# TR808_Project-2.net
KiCad netlist of a schematic drawn in EAGLE
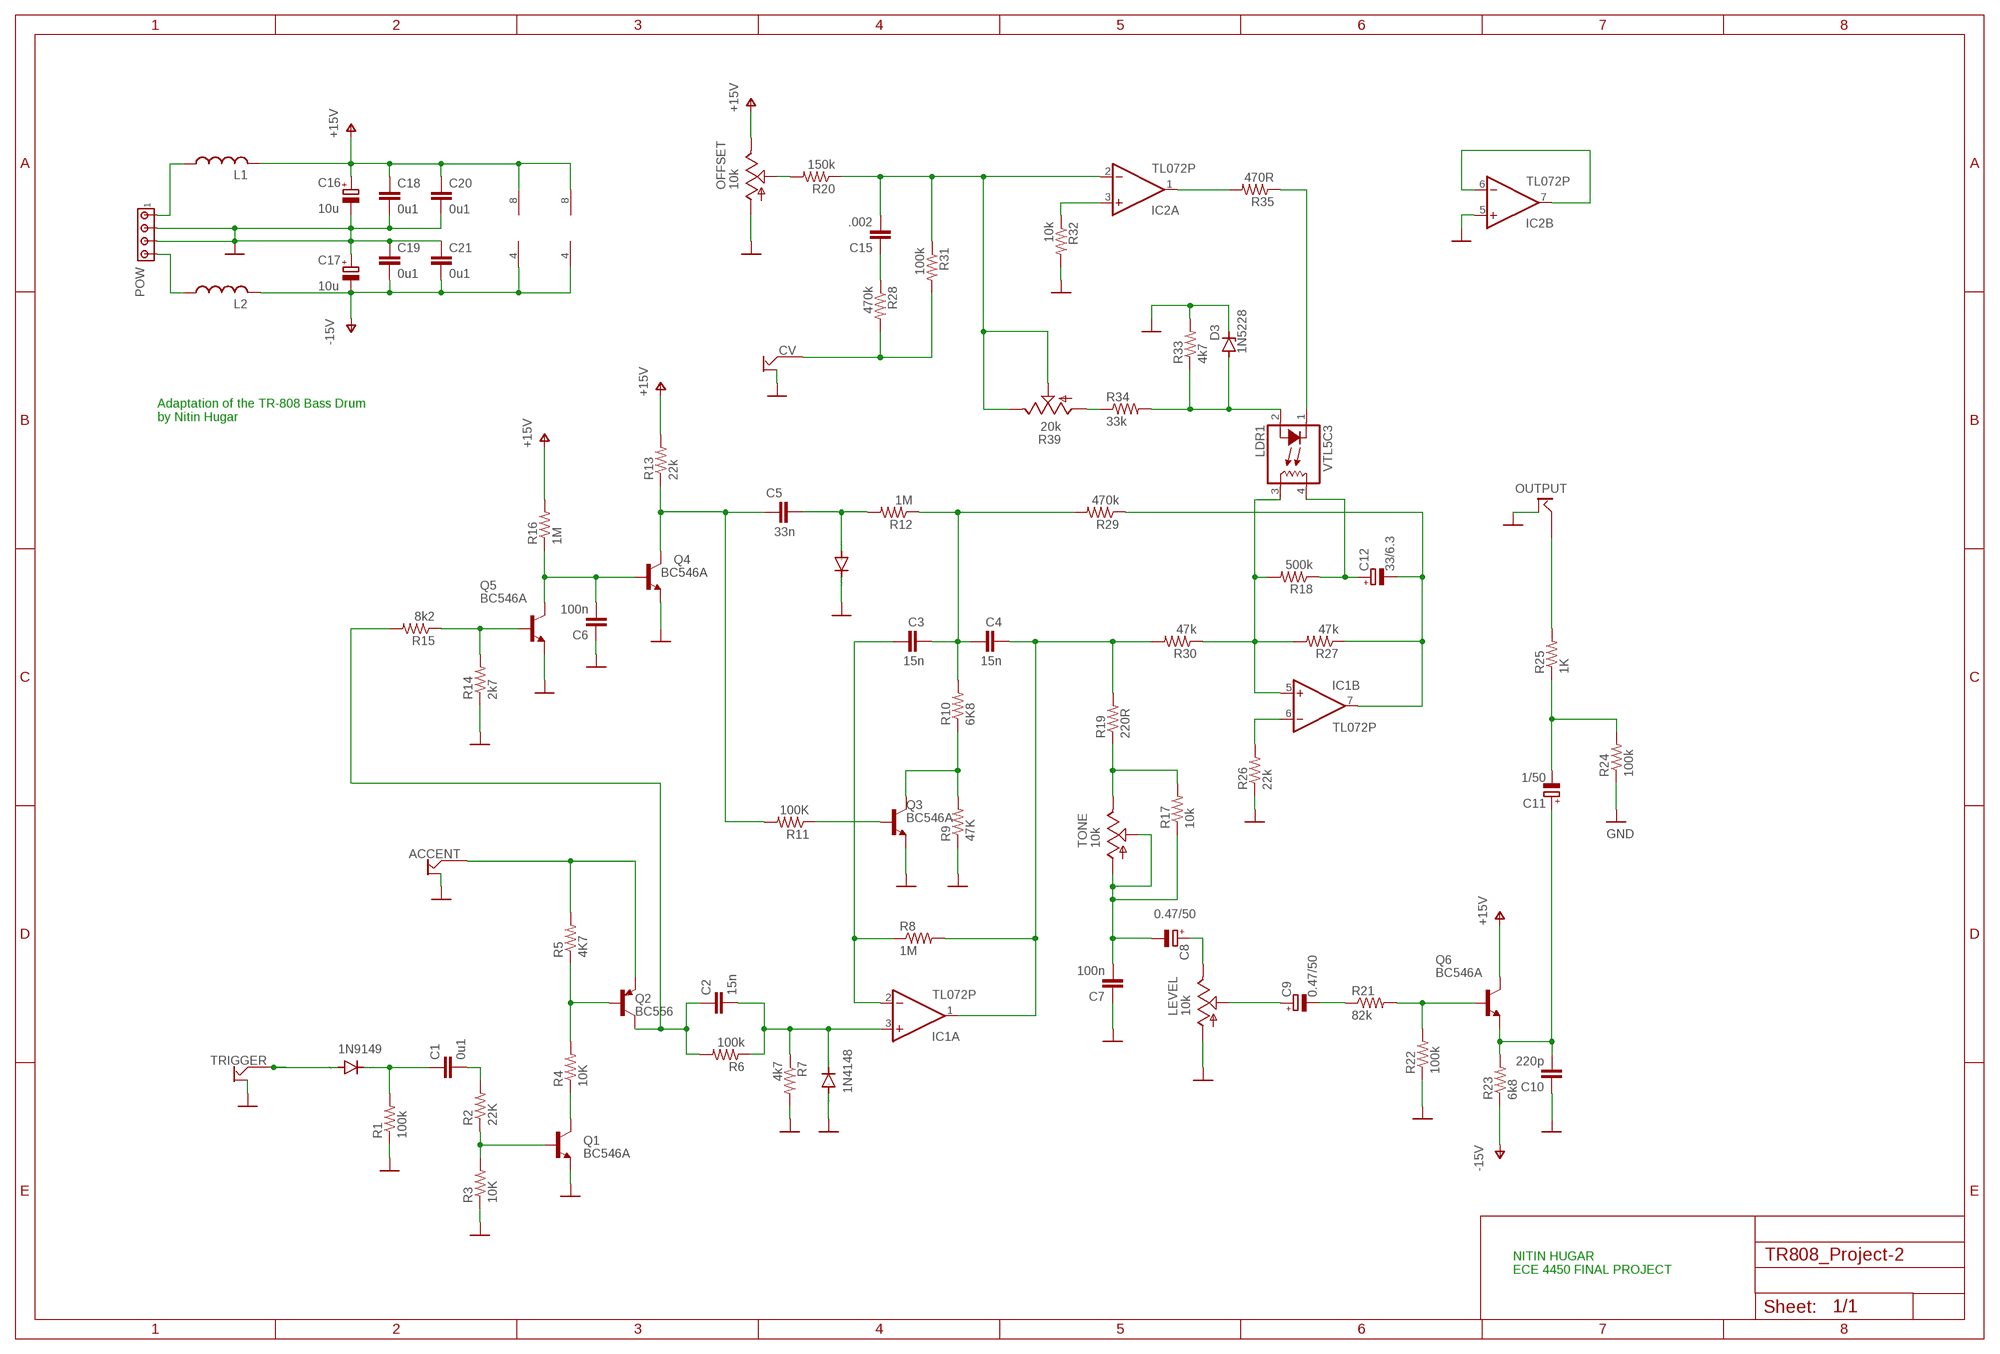
[diagram p0: schematic, sheet 1]

(export (version "E")
  (design (tool "Eeschema 10.0.6"))
  (components
    (comp (ref "1N4148")
      (value "1N4148")
      (footprint "eagle-import:DO35-10")
      (libsource (lib "eagle-import") (part "1N4148DO35-10"))
    )
    (comp (ref "ACCENT")
      (value "OFFBOARD2JACKALT_AARON")
      (footprint "eagle-import:OFFBOARD2JACKALT")
      (libsource (lib "eagle-import") (part "OFFBOARD2JACKALT_AARON"))
    )
    (comp (ref "C1")
      (value "0u1")
      (footprint "eagle-import:C050-025X075")
      (libsource (lib "eagle-import") (part "C-EU050-025X075"))
    )
    (comp (ref "C2")
      (value "15n")
      (footprint "eagle-import:C050-025X075")
      (libsource (lib "eagle-import") (part "C-EU050-025X075"))
    )
    (comp (ref "C3")
      (value "15n")
      (footprint "eagle-import:C050-025X075")
      (libsource (lib "eagle-import") (part "C-EU050-025X075"))
    )
    (comp (ref "C4")
      (value "15n")
      (footprint "eagle-import:C050-025X075")
      (libsource (lib "eagle-import") (part "C-EU050-025X075"))
    )
    (comp (ref "C5")
      (value "33n")
      (footprint "eagle-import:C050-025X075")
      (libsource (lib "eagle-import") (part "C-EU050-025X075"))
    )
    (comp (ref "C6")
      (value "100n")
      (footprint "eagle-import:C050-025X075")
      (libsource (lib "eagle-import") (part "C-EU050-025X075"))
    )
    (comp (ref "C7")
      (value "100n")
      (footprint "eagle-import:C050-025X075")
      (libsource (lib "eagle-import") (part "C-EU050-025X075"))
    )
    (comp (ref "C8")
      (value "0.47/50")
      (footprint "eagle-import:E1,8-4")
      (libsource (lib "eagle-import") (part "CPOL-EUE1.8-4"))
    )
    (comp (ref "C9")
      (value "0.47/50")
      (footprint "eagle-import:E1,8-4")
      (libsource (lib "eagle-import") (part "CPOL-EUE1.8-4"))
    )
    (comp (ref "C10")
      (value "220p")
      (footprint "eagle-import:C050-025X075")
      (libsource (lib "eagle-import") (part "C-EU050-025X075"))
    )
    (comp (ref "C11")
      (value "1/50")
      (footprint "eagle-import:E1,8-4")
      (libsource (lib "eagle-import") (part "CPOL-EUE1.8-4"))
    )
    (comp (ref "C12")
      (value "33/6.3")
      (footprint "eagle-import:E1,8-4")
      (libsource (lib "eagle-import") (part "CPOL-EUE1.8-4"))
    )
    (comp (ref "C15")
      (value ".002")
      (footprint "eagle-import:C050-025X075")
      (libsource (lib "eagle-import") (part "C-EU050-025X075"))
    )
    (comp (ref "C16")
      (value "10u")
      (footprint "eagle-import:E1,8-4")
      (libsource (lib "eagle-import") (part "CPOL-EUE1.8-4"))
    )
    (comp (ref "C17")
      (value "10u")
      (footprint "eagle-import:E1,8-4")
      (libsource (lib "eagle-import") (part "CPOL-EUE1.8-4"))
    )
    (comp (ref "C18")
      (value "0u1")
      (footprint "eagle-import:C050-025X075")
      (libsource (lib "eagle-import") (part "C-EU050-025X075"))
    )
    (comp (ref "C19")
      (value "0u1")
      (footprint "eagle-import:C050-025X075")
      (libsource (lib "eagle-import") (part "C-EU050-025X075"))
    )
    (comp (ref "C20")
      (value "0u1")
      (footprint "eagle-import:C050-025X075")
      (libsource (lib "eagle-import") (part "C-EU050-025X075"))
    )
    (comp (ref "C21")
      (value "0u1")
      (footprint "eagle-import:C050-025X075")
      (libsource (lib "eagle-import") (part "C-EU050-025X075"))
    )
    (comp (ref "CV")
      (value "OFFBOARD2JACKALT_AARON")
      (footprint "eagle-import:OFFBOARD2JACKALT")
      (libsource (lib "eagle-import") (part "OFFBOARD2JACKALT_AARON"))
    )
    (comp (ref "D1")
      (value "1N9149")
      (footprint "eagle-import:D-10")
      (libsource (lib "eagle-import") (part "DIODE-D-10"))
    )
    (comp (ref "D2")
      (value "1N4148")
      (footprint "eagle-import:DO35-10")
      (libsource (lib "eagle-import") (part "1N4148DO35-10"))
    )
    (comp (ref "D3")
      (value "1N5228")
      (footprint "eagle-import:C1702-15")
      (libsource (lib "eagle-import") (part "ZENER-DIODEC1702-15"))
    )
    (comp (ref "IC1")
      (value "TL072P")
      (footprint "eagle-import:DIL08")
      (libsource (lib "eagle-import") (part "TL072P"))
    )
    (comp (ref "IC2")
      (value "TL072P")
      (footprint "eagle-import:DIL08")
      (libsource (lib "eagle-import") (part "TL072P"))
    )
    (comp (ref "L1")
      (value "L-US0207/10")
      (footprint "eagle-import:0207_10")
      (libsource (lib "eagle-import") (part "L-US0207/10"))
    )
    (comp (ref "L2")
      (value "L-US0207/10")
      (footprint "eagle-import:0207_10")
      (libsource (lib "eagle-import") (part "L-US0207/10"))
    )
    (comp (ref "LDR1")
      (value "VTL5C3")
      (footprint "eagle-import:VTL5C")
      (fields (field (name "MF") "VACTEC PHOTO") (field (name "MPN") "VTL5C9"))
      (libsource (lib "eagle-import") (part "VTL5C9"))
    )
    (comp (ref "LEVEL")
      (value "10k")
      (footprint "eagle-import:B64Y")
      (libsource (lib "eagle-import") (part "TRIM_US-B64Y"))
    )
    (comp (ref "OFFSET")
      (value "10k")
      (footprint "eagle-import:B64Y")
      (libsource (lib "eagle-import") (part "TRIM_US-B64Y"))
    )
    (comp (ref "OUTPUT")
      (value "OFFBOARD2JACKALT_AARON")
      (footprint "eagle-import:OFFBOARD2JACKALT")
      (libsource (lib "eagle-import") (part "OFFBOARD2JACKALT_AARON"))
    )
    (comp (ref "POW")
      (value "MTA04-156")
      (footprint "eagle-import:1X4MTA")
      (libsource (lib "eagle-import") (part "MTA04-156"))
    )
    (comp (ref "Q1")
      (value "BC546A")
      (footprint "eagle-import:TO92-EBC")
      (libsource (lib "eagle-import") (part "BC546A"))
    )
    (comp (ref "Q2")
      (value "BC556")
      (footprint "eagle-import:TO92-EBC")
      (libsource (lib "eagle-import") (part "BC556"))
    )
    (comp (ref "Q3")
      (value "BC546A")
      (footprint "eagle-import:TO92-EBC")
      (libsource (lib "eagle-import") (part "BC546A"))
    )
    (comp (ref "Q4")
      (value "BC546A")
      (footprint "eagle-import:TO92-EBC")
      (libsource (lib "eagle-import") (part "BC546A"))
    )
    (comp (ref "Q5")
      (value "BC546A")
      (footprint "eagle-import:TO92-EBC")
      (libsource (lib "eagle-import") (part "BC546A"))
    )
    (comp (ref "Q6")
      (value "BC546A")
      (footprint "eagle-import:TO92-EBC")
      (libsource (lib "eagle-import") (part "BC546A"))
    )
    (comp (ref "R1")
      (value "100k")
      (footprint "eagle-import:0207_10")
      (libsource (lib "eagle-import") (part "R-US_0207/10"))
    )
    (comp (ref "R2")
      (value "22K")
      (footprint "eagle-import:0207_10")
      (libsource (lib "eagle-import") (part "R-US_0207/10"))
    )
    (comp (ref "R3")
      (value "10K")
      (footprint "eagle-import:0207_10")
      (libsource (lib "eagle-import") (part "R-US_0207/10"))
    )
    (comp (ref "R4")
      (value "10K")
      (footprint "eagle-import:0207_10")
      (libsource (lib "eagle-import") (part "R-US_0207/10"))
    )
    (comp (ref "R5")
      (value "4K7")
      (footprint "eagle-import:0207_10")
      (libsource (lib "eagle-import") (part "R-US_0207/10"))
    )
    (comp (ref "R6")
      (value "100k")
      (footprint "eagle-import:0207_10")
      (libsource (lib "eagle-import") (part "R-US_0207/10"))
    )
    (comp (ref "R7")
      (value "4k7")
      (footprint "eagle-import:0207_10")
      (libsource (lib "eagle-import") (part "R-US_0207/10"))
    )
    (comp (ref "R8")
      (value "1M")
      (footprint "eagle-import:0207_10")
      (libsource (lib "eagle-import") (part "R-US_0207/10"))
    )
    (comp (ref "R9")
      (value "47K")
      (footprint "eagle-import:0207_10")
      (libsource (lib "eagle-import") (part "R-US_0207/10"))
    )
    (comp (ref "R10")
      (value "6K8")
      (footprint "eagle-import:0207_10")
      (libsource (lib "eagle-import") (part "R-US_0207/10"))
    )
    (comp (ref "R11")
      (value "100K")
      (footprint "eagle-import:0207_10")
      (libsource (lib "eagle-import") (part "R-US_0207/10"))
    )
    (comp (ref "R12")
      (value "1M")
      (footprint "eagle-import:0207_10")
      (libsource (lib "eagle-import") (part "R-US_0207/10"))
    )
    (comp (ref "R13")
      (value "22k")
      (footprint "eagle-import:0207_10")
      (libsource (lib "eagle-import") (part "R-US_0207/10"))
    )
    (comp (ref "R14")
      (value "2k7")
      (footprint "eagle-import:0207_10")
      (libsource (lib "eagle-import") (part "R-US_0207/10"))
    )
    (comp (ref "R15")
      (value "8k2")
      (footprint "eagle-import:0207_10")
      (libsource (lib "eagle-import") (part "R-US_0207/10"))
    )
    (comp (ref "R16")
      (value "1M")
      (footprint "eagle-import:0207_10")
      (libsource (lib "eagle-import") (part "R-US_0207/10"))
    )
    (comp (ref "R17")
      (value "10k")
      (footprint "eagle-import:0207_10")
      (libsource (lib "eagle-import") (part "R-US_0207/10"))
    )
    (comp (ref "R18")
      (value "500k")
      (footprint "eagle-import:0207_10")
      (libsource (lib "eagle-import") (part "R-US_0207/10"))
    )
    (comp (ref "R19")
      (value "220R")
      (footprint "eagle-import:0207_10")
      (libsource (lib "eagle-import") (part "R-US_0207/10"))
    )
    (comp (ref "R20")
      (value "150k")
      (footprint "eagle-import:0207_10")
      (libsource (lib "eagle-import") (part "R-US_0207/10"))
    )
    (comp (ref "R21")
      (value "82k")
      (footprint "eagle-import:0207_10")
      (libsource (lib "eagle-import") (part "R-US_0207/10"))
    )
    (comp (ref "R22")
      (value "100k")
      (footprint "eagle-import:0207_10")
      (libsource (lib "eagle-import") (part "R-US_0207/10"))
    )
    (comp (ref "R23")
      (value "6k8")
      (footprint "eagle-import:0207_10")
      (libsource (lib "eagle-import") (part "R-US_0207/10"))
    )
    (comp (ref "R24")
      (value "100k")
      (footprint "eagle-import:0207_10")
      (libsource (lib "eagle-import") (part "R-US_0207/10"))
    )
    (comp (ref "R25")
      (value "1K")
      (footprint "eagle-import:0207_10")
      (libsource (lib "eagle-import") (part "R-US_0207/10"))
    )
    (comp (ref "R26")
      (value "22k")
      (footprint "eagle-import:0207_10")
      (libsource (lib "eagle-import") (part "R-US_0207/10"))
    )
    (comp (ref "R27")
      (value "47k")
      (footprint "eagle-import:0207_10")
      (libsource (lib "eagle-import") (part "R-US_0207/10"))
    )
    (comp (ref "R28")
      (value "470k")
      (footprint "eagle-import:0207_10")
      (libsource (lib "eagle-import") (part "R-US_0207/10"))
    )
    (comp (ref "R29")
      (value "470k")
      (footprint "eagle-import:0207_10")
      (libsource (lib "eagle-import") (part "R-US_0207/10"))
    )
    (comp (ref "R30")
      (value "47k")
      (footprint "eagle-import:0207_10")
      (libsource (lib "eagle-import") (part "R-US_0207/10"))
    )
    (comp (ref "R31")
      (value "100k")
      (footprint "eagle-import:0207_10")
      (libsource (lib "eagle-import") (part "R-US_0207/10"))
    )
    (comp (ref "R32")
      (value "10k")
      (footprint "eagle-import:0207_10")
      (libsource (lib "eagle-import") (part "R-US_0207/10"))
    )
    (comp (ref "R33")
      (value "4k7")
      (footprint "eagle-import:0207_10")
      (libsource (lib "eagle-import") (part "R-US_0207/10"))
    )
    (comp (ref "R34")
      (value "33k")
      (footprint "eagle-import:0207_10")
      (libsource (lib "eagle-import") (part "R-US_0207/10"))
    )
    (comp (ref "R35")
      (value "470R")
      (footprint "eagle-import:0207_10")
      (libsource (lib "eagle-import") (part "R-US_0207/10"))
    )
    (comp (ref "R39")
      (value "20k")
      (footprint "eagle-import:B64Y")
      (libsource (lib "eagle-import") (part "TRIM_US-B64Y"))
    )
    (comp (ref "TONE")
      (value "10k")
      (footprint "eagle-import:B64Y")
      (libsource (lib "eagle-import") (part "TRIM_US-B64Y"))
    )
    (comp (ref "TRIGGER")
      (value "OFFBOARD2JACKALT_AARON")
      (footprint "eagle-import:OFFBOARD2JACKALT")
      (libsource (lib "eagle-import") (part "OFFBOARD2JACKALT_AARON"))
    )
  )
  (nets
    (net (code "1") (name "+15V") (class "Default")
      (node (ref "C16") (pin "+") (pinfunction "+_+") (pintype "passive"))
      (node (ref "C18") (pin "1") (pinfunction "1_1") (pintype "passive"))
      (node (ref "C20") (pin "1") (pinfunction "1_1") (pintype "passive"))
      (node (ref "IC1") (pin "8") (pinfunction "V+_8") (pintype "power_in"))
      (node (ref "IC2") (pin "8") (pinfunction "V+_8") (pintype "power_in"))
      (node (ref "L1") (pin "2") (pinfunction "2_2") (pintype "passive"))
      (node (ref "OFFSET") (pin "E") (pinfunction "E_E") (pintype "passive"))
      (node (ref "Q6") (pin "C") (pinfunction "C_C") (pintype "passive"))
      (node (ref "R13") (pin "2") (pinfunction "2_2") (pintype "passive"))
      (node (ref "R16") (pin "2") (pinfunction "2_2") (pintype "passive"))
    )
    (net (code "2") (name "-15V") (class "Default")
      (node (ref "C17") (pin "-") (pinfunction "-_-") (pintype "passive"))
      (node (ref "C19") (pin "2") (pinfunction "2_2") (pintype "passive"))
      (node (ref "C21") (pin "2") (pinfunction "2_2") (pintype "passive"))
      (node (ref "IC1") (pin "4") (pinfunction "V-_4") (pintype "power_in"))
      (node (ref "IC2") (pin "4") (pinfunction "V-_4") (pintype "power_in"))
      (node (ref "L2") (pin "2") (pinfunction "2_2") (pintype "passive"))
      (node (ref "R23") (pin "1") (pinfunction "1_1") (pintype "passive"))
    )
    (net (code "3") (name "GND") (class "Default")
      (node (ref "1N4148") (pin "A") (pinfunction "A_A") (pintype "passive"))
      (node (ref "ACCENT") (pin "GND") (pinfunction "GND_GND") (pintype "passive"))
      (node (ref "C10") (pin "1") (pinfunction "1_1") (pintype "passive"))
      (node (ref "C16") (pin "-") (pinfunction "-_-") (pintype "passive"))
      (node (ref "C17") (pin "+") (pinfunction "+_+") (pintype "passive"))
      (node (ref "C18") (pin "2") (pinfunction "2_2") (pintype "passive"))
      (node (ref "C19") (pin "1") (pinfunction "1_1") (pintype "passive"))
      (node (ref "C20") (pin "2") (pinfunction "2_2") (pintype "passive"))
      (node (ref "C21") (pin "1") (pinfunction "1_1") (pintype "passive"))
      (node (ref "C6") (pin "1") (pinfunction "1_1") (pintype "passive"))
      (node (ref "C7") (pin "1") (pinfunction "1_1") (pintype "passive"))
      (node (ref "CV") (pin "GND") (pinfunction "GND_GND") (pintype "passive"))
      (node (ref "D2") (pin "C") (pinfunction "C_C") (pintype "passive"))
      (node (ref "D3") (pin "C") (pinfunction "C_C") (pintype "passive"))
      (node (ref "IC2") (pin "5") (pinfunction "+IN_5") (pintype "input"))
      (node (ref "LEVEL") (pin "A") (pinfunction "A_A") (pintype "passive"))
      (node (ref "OFFSET") (pin "A") (pinfunction "A_A") (pintype "passive"))
      (node (ref "OUTPUT") (pin "GND") (pinfunction "GND_GND") (pintype "passive"))
      (node (ref "POW") (pin "2") (pinfunction "2_2") (pintype "passive"))
      (node (ref "POW") (pin "3") (pinfunction "3_3") (pintype "passive"))
      (node (ref "Q1") (pin "E") (pinfunction "E_E") (pintype "passive"))
      (node (ref "Q3") (pin "E") (pinfunction "E_E") (pintype "passive"))
      (node (ref "Q4") (pin "E") (pinfunction "E_E") (pintype "passive"))
      (node (ref "Q5") (pin "E") (pinfunction "E_E") (pintype "passive"))
      (node (ref "R1") (pin "1") (pinfunction "1_1") (pintype "passive"))
      (node (ref "R14") (pin "1") (pinfunction "1_1") (pintype "passive"))
      (node (ref "R22") (pin "1") (pinfunction "1_1") (pintype "passive"))
      (node (ref "R24") (pin "1") (pinfunction "1_1") (pintype "passive"))
      (node (ref "R26") (pin "1") (pinfunction "1_1") (pintype "passive"))
      (node (ref "R3") (pin "1") (pinfunction "1_1") (pintype "passive"))
      (node (ref "R32") (pin "2") (pinfunction "2_2") (pintype "passive"))
      (node (ref "R33") (pin "2") (pinfunction "2_2") (pintype "passive"))
      (node (ref "R7") (pin "2") (pinfunction "2_2") (pintype "passive"))
      (node (ref "R9") (pin "1") (pinfunction "1_1") (pintype "passive"))
      (node (ref "TRIGGER") (pin "GND") (pinfunction "GND_GND") (pintype "passive"))
    )
    (net (code "4") (name "Net-(ACCENT-PadSIGNAL)") (class "Default")
      (node (ref "ACCENT") (pin "SIGNAL") (pinfunction "SIGNAL_SIGNAL") (pintype "passive"))
      (node (ref "Q2") (pin "E") (pinfunction "E_E") (pintype "passive"))
      (node (ref "R5") (pin "2") (pinfunction "2_2") (pintype "passive"))
    )
    (net (code "5") (name "Net-(C1-Pad1)") (class "Default")
      (node (ref "C1") (pin "1") (pinfunction "1_1") (pintype "passive"))
      (node (ref "D1") (pin "C") (pinfunction "C_C") (pintype "passive"))
      (node (ref "R1") (pin "2") (pinfunction "2_2") (pintype "passive"))
    )
    (net (code "6") (name "Net-(C1-Pad2)") (class "Default")
      (node (ref "C1") (pin "2") (pinfunction "2_2") (pintype "passive"))
      (node (ref "R2") (pin "2") (pinfunction "2_2") (pintype "passive"))
    )
    (net (code "7") (name "Net-(C2-Pad1)") (class "Default")
      (node (ref "C2") (pin "1") (pinfunction "1_1") (pintype "passive"))
      (node (ref "Q2") (pin "C") (pinfunction "C_C") (pintype "passive"))
      (node (ref "R15") (pin "2") (pinfunction "2_2") (pintype "passive"))
      (node (ref "R6") (pin "2") (pinfunction "2_2") (pintype "passive"))
    )
    (net (code "8") (name "Net-(C3-Pad2)") (class "Default")
      (node (ref "C3") (pin "2") (pinfunction "2_2") (pintype "passive"))
      (node (ref "C4") (pin "1") (pinfunction "1_1") (pintype "passive"))
      (node (ref "R10") (pin "2") (pinfunction "2_2") (pintype "passive"))
      (node (ref "R12") (pin "1") (pinfunction "1_1") (pintype "passive"))
      (node (ref "R29") (pin "2") (pinfunction "2_2") (pintype "passive"))
    )
    (net (code "9") (name "Net-(C5-Pad1)") (class "Default")
      (node (ref "C5") (pin "1") (pinfunction "1_1") (pintype "passive"))
      (node (ref "Q4") (pin "C") (pinfunction "C_C") (pintype "passive"))
      (node (ref "R11") (pin "2") (pinfunction "2_2") (pintype "passive"))
      (node (ref "R13") (pin "1") (pinfunction "1_1") (pintype "passive"))
    )
    (net (code "10") (name "Net-(C5-Pad2)") (class "Default")
      (node (ref "C5") (pin "2") (pinfunction "2_2") (pintype "passive"))
      (node (ref "D2") (pin "A") (pinfunction "A_A") (pintype "passive"))
      (node (ref "R12") (pin "2") (pinfunction "2_2") (pintype "passive"))
    )
    (net (code "11") (name "Net-(C6-Pad2)") (class "Default")
      (node (ref "C6") (pin "2") (pinfunction "2_2") (pintype "passive"))
      (node (ref "Q4") (pin "B") (pinfunction "B_B") (pintype "passive"))
      (node (ref "Q5") (pin "C") (pinfunction "C_C") (pintype "passive"))
      (node (ref "R16") (pin "1") (pinfunction "1_1") (pintype "passive"))
    )
    (net (code "12") (name "Net-(C7-Pad2)") (class "Default")
      (node (ref "C7") (pin "2") (pinfunction "2_2") (pintype "passive"))
      (node (ref "C8") (pin "-") (pinfunction "-_-") (pintype "passive"))
      (node (ref "R17") (pin "1") (pinfunction "1_1") (pintype "passive"))
      (node (ref "TONE") (pin "A") (pinfunction "A_A") (pintype "passive"))
      (node (ref "TONE") (pin "S") (pinfunction "S_S") (pintype "passive"))
    )
    (net (code "13") (name "Net-(C8-Pad+)") (class "Default")
      (node (ref "C8") (pin "+") (pinfunction "+_+") (pintype "passive"))
      (node (ref "LEVEL") (pin "E") (pinfunction "E_E") (pintype "passive"))
    )
    (net (code "14") (name "Net-(C9-Pad+)") (class "Default")
      (node (ref "C9") (pin "+") (pinfunction "+_+") (pintype "passive"))
      (node (ref "LEVEL") (pin "S") (pinfunction "S_S") (pintype "passive"))
    )
    (net (code "15") (name "Net-(C9-Pad-)") (class "Default")
      (node (ref "C9") (pin "-") (pinfunction "-_-") (pintype "passive"))
      (node (ref "R21") (pin "1") (pinfunction "1_1") (pintype "passive"))
    )
    (net (code "16") (name "Net-(C10-Pad2)") (class "Default")
      (node (ref "C10") (pin "2") (pinfunction "2_2") (pintype "passive"))
      (node (ref "C11") (pin "+") (pinfunction "+_+") (pintype "passive"))
      (node (ref "Q6") (pin "E") (pinfunction "E_E") (pintype "passive"))
      (node (ref "R23") (pin "2") (pinfunction "2_2") (pintype "passive"))
    )
    (net (code "17") (name "Net-(C11-Pad-)") (class "Default")
      (node (ref "C11") (pin "-") (pinfunction "-_-") (pintype "passive"))
      (node (ref "R24") (pin "2") (pinfunction "2_2") (pintype "passive"))
      (node (ref "R25") (pin "1") (pinfunction "1_1") (pintype "passive"))
    )
    (net (code "18") (name "Net-(C15-Pad1)") (class "Default")
      (node (ref "C15") (pin "1") (pinfunction "1_1") (pintype "passive"))
      (node (ref "R28") (pin "1") (pinfunction "1_1") (pintype "passive"))
    )
    (net (code "19") (name "Net-(CV-PadSIGNAL)") (class "Default")
      (node (ref "CV") (pin "SIGNAL") (pinfunction "SIGNAL_SIGNAL") (pintype "passive"))
      (node (ref "R28") (pin "2") (pinfunction "2_2") (pintype "passive"))
      (node (ref "R31") (pin "2") (pinfunction "2_2") (pintype "passive"))
    )
    (net (code "20") (name "Net-(D1-PadA)") (class "Default")
      (node (ref "D1") (pin "A") (pinfunction "A_A") (pintype "passive"))
      (node (ref "TRIGGER") (pin "SIGNAL") (pinfunction "SIGNAL_SIGNAL") (pintype "passive"))
    )
    (net (code "21") (name "Net-(IC1A-+IN)") (class "Default")
      (node (ref "1N4148") (pin "C") (pinfunction "C_C") (pintype "passive"))
      (node (ref "C2") (pin "2") (pinfunction "2_2") (pintype "passive"))
      (node (ref "IC1") (pin "3") (pinfunction "+IN_3") (pintype "input"))
      (node (ref "R6") (pin "1") (pinfunction "1_1") (pintype "passive"))
      (node (ref "R7") (pin "1") (pinfunction "1_1") (pintype "passive"))
    )
    (net (code "22") (name "Net-(IC1A--IN)") (class "Default")
      (node (ref "C3") (pin "1") (pinfunction "1_1") (pintype "passive"))
      (node (ref "IC1") (pin "2") (pinfunction "-IN_2") (pintype "input"))
      (node (ref "R8") (pin "1") (pinfunction "1_1") (pintype "passive"))
    )
    (net (code "23") (name "Net-(IC1A-OUT)") (class "Default")
      (node (ref "C4") (pin "2") (pinfunction "2_2") (pintype "passive"))
      (node (ref "IC1") (pin "1") (pinfunction "OUT_1") (pintype "output"))
      (node (ref "R19") (pin "2") (pinfunction "2_2") (pintype "passive"))
      (node (ref "R30") (pin "2") (pinfunction "2_2") (pintype "passive"))
      (node (ref "R8") (pin "2") (pinfunction "2_2") (pintype "passive"))
    )
    (net (code "24") (name "Net-(IC1B-+IN)") (class "Default")
      (node (ref "IC1") (pin "5") (pinfunction "+IN_5") (pintype "input"))
      (node (ref "LDR1") (pin "3") (pinfunction "L1_3") (pintype "passive"))
      (node (ref "R18") (pin "2") (pinfunction "2_2") (pintype "passive"))
      (node (ref "R27") (pin "2") (pinfunction "2_2") (pintype "passive"))
      (node (ref "R30") (pin "1") (pinfunction "1_1") (pintype "passive"))
    )
    (net (code "25") (name "Net-(IC1B--IN)") (class "Default")
      (node (ref "IC1") (pin "6") (pinfunction "-IN_6") (pintype "input"))
      (node (ref "R26") (pin "2") (pinfunction "2_2") (pintype "passive"))
    )
    (net (code "26") (name "Net-(IC1B-OUT)") (class "Default")
      (node (ref "C12") (pin "-") (pinfunction "-_-") (pintype "passive"))
      (node (ref "IC1") (pin "7") (pinfunction "OUT_7") (pintype "output"))
      (node (ref "R27") (pin "1") (pinfunction "1_1") (pintype "passive"))
      (node (ref "R29") (pin "1") (pinfunction "1_1") (pintype "passive"))
    )
    (net (code "27") (name "Net-(IC2A-+IN)") (class "Default")
      (node (ref "IC2") (pin "3") (pinfunction "+IN_3") (pintype "input"))
      (node (ref "R32") (pin "1") (pinfunction "1_1") (pintype "passive"))
    )
    (net (code "28") (name "Net-(IC2A--IN)") (class "Default")
      (node (ref "C15") (pin "2") (pinfunction "2_2") (pintype "passive"))
      (node (ref "IC2") (pin "2") (pinfunction "-IN_2") (pintype "input"))
      (node (ref "R20") (pin "1") (pinfunction "1_1") (pintype "passive"))
      (node (ref "R31") (pin "1") (pinfunction "1_1") (pintype "passive"))
      (node (ref "R39") (pin "E") (pinfunction "E_E") (pintype "passive"))
      (node (ref "R39") (pin "S") (pinfunction "S_S") (pintype "passive"))
    )
    (net (code "29") (name "Net-(IC2A-OUT)") (class "Default")
      (node (ref "IC2") (pin "1") (pinfunction "OUT_1") (pintype "output"))
      (node (ref "R35") (pin "2") (pinfunction "2_2") (pintype "passive"))
    )
    (net (code "30") (name "Net-(IC2B--IN)") (class "Default")
      (node (ref "IC2") (pin "6") (pinfunction "-IN_6") (pintype "input"))
      (node (ref "IC2") (pin "7") (pinfunction "OUT_7") (pintype "output"))
    )
    (net (code "31") (name "Net-(L1-Pad1)") (class "Default")
      (node (ref "L1") (pin "1") (pinfunction "1_1") (pintype "passive"))
      (node (ref "POW") (pin "1") (pinfunction "1_1") (pintype "passive"))
    )
    (net (code "32") (name "Net-(L2-Pad1)") (class "Default")
      (node (ref "L2") (pin "1") (pinfunction "1_1") (pintype "passive"))
      (node (ref "POW") (pin "4") (pinfunction "4_4") (pintype "passive"))
    )
    (net (code "33") (name "Net-(LDR1-A)") (class "Default")
      (node (ref "D3") (pin "A") (pinfunction "A_A") (pintype "passive"))
      (node (ref "LDR1") (pin "2") (pinfunction "A_2") (pintype "passive"))
      (node (ref "R33") (pin "1") (pinfunction "1_1") (pintype "passive"))
      (node (ref "R34") (pin "2") (pinfunction "2_2") (pintype "passive"))
    )
    (net (code "34") (name "Net-(LDR1-C)") (class "Default")
      (node (ref "LDR1") (pin "1") (pinfunction "C_1") (pintype "passive"))
      (node (ref "R35") (pin "1") (pinfunction "1_1") (pintype "passive"))
    )
    (net (code "35") (name "Net-(LDR1-L2)") (class "Default")
      (node (ref "C12") (pin "+") (pinfunction "+_+") (pintype "passive"))
      (node (ref "LDR1") (pin "4") (pinfunction "L2_4") (pintype "passive"))
      (node (ref "R18") (pin "1") (pinfunction "1_1") (pintype "passive"))
    )
    (net (code "36") (name "Net-(OFFSET-PadS)") (class "Default")
      (node (ref "OFFSET") (pin "S") (pinfunction "S_S") (pintype "passive"))
      (node (ref "R20") (pin "2") (pinfunction "2_2") (pintype "passive"))
    )
    (net (code "37") (name "Net-(OUTPUT-PadSIGNAL)") (class "Default")
      (node (ref "OUTPUT") (pin "SIGNAL") (pinfunction "SIGNAL_SIGNAL") (pintype "passive"))
      (node (ref "R25") (pin "2") (pinfunction "2_2") (pintype "passive"))
    )
    (net (code "38") (name "Net-(Q1-PadB)") (class "Default")
      (node (ref "Q1") (pin "B") (pinfunction "B_B") (pintype "passive"))
      (node (ref "R2") (pin "1") (pinfunction "1_1") (pintype "passive"))
      (node (ref "R3") (pin "2") (pinfunction "2_2") (pintype "passive"))
    )
    (net (code "39") (name "Net-(Q1-PadC)") (class "Default")
      (node (ref "Q1") (pin "C") (pinfunction "C_C") (pintype "passive"))
      (node (ref "R4") (pin "1") (pinfunction "1_1") (pintype "passive"))
    )
    (net (code "40") (name "Net-(Q2-PadB)") (class "Default")
      (node (ref "Q2") (pin "B") (pinfunction "B_B") (pintype "passive"))
      (node (ref "R4") (pin "2") (pinfunction "2_2") (pintype "passive"))
      (node (ref "R5") (pin "1") (pinfunction "1_1") (pintype "passive"))
    )
    (net (code "41") (name "Net-(Q3-PadB)") (class "Default")
      (node (ref "Q3") (pin "B") (pinfunction "B_B") (pintype "passive"))
      (node (ref "R11") (pin "1") (pinfunction "1_1") (pintype "passive"))
    )
    (net (code "42") (name "Net-(Q3-PadC)") (class "Default")
      (node (ref "Q3") (pin "C") (pinfunction "C_C") (pintype "passive"))
      (node (ref "R10") (pin "1") (pinfunction "1_1") (pintype "passive"))
      (node (ref "R9") (pin "2") (pinfunction "2_2") (pintype "passive"))
    )
    (net (code "43") (name "Net-(Q5-PadB)") (class "Default")
      (node (ref "Q5") (pin "B") (pinfunction "B_B") (pintype "passive"))
      (node (ref "R14") (pin "2") (pinfunction "2_2") (pintype "passive"))
      (node (ref "R15") (pin "1") (pinfunction "1_1") (pintype "passive"))
    )
    (net (code "44") (name "Net-(Q6-PadB)") (class "Default")
      (node (ref "Q6") (pin "B") (pinfunction "B_B") (pintype "passive"))
      (node (ref "R21") (pin "2") (pinfunction "2_2") (pintype "passive"))
      (node (ref "R22") (pin "2") (pinfunction "2_2") (pintype "passive"))
    )
    (net (code "45") (name "Net-(R17-Pad2)") (class "Default")
      (node (ref "R17") (pin "2") (pinfunction "2_2") (pintype "passive"))
      (node (ref "R19") (pin "1") (pinfunction "1_1") (pintype "passive"))
      (node (ref "TONE") (pin "E") (pinfunction "E_E") (pintype "passive"))
    )
    (net (code "46") (name "Net-(R34-Pad1)") (class "Default")
      (node (ref "R34") (pin "1") (pinfunction "1_1") (pintype "passive"))
      (node (ref "R39") (pin "A") (pinfunction "A_A") (pintype "passive"))
    )
  )
)
